# 800U_R3N3_SONSER_V1_0.net
KiCad netlist of a schematic drawn in Altium Designer
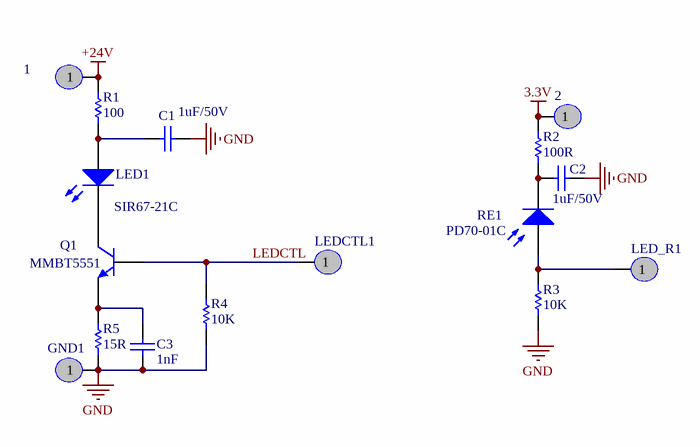
[diagram p0: 800U R3N3_SONSER_V1.0.SchDoc]

(export (version "E")
  (design (tool "Eeschema 10.0.6"))
  (components
    (comp (ref "1") (value "~") (footprint "HOLE_SMD") (libsource (lib "MODBUS_V1.0") (part "焊盘")))
    (comp (ref "2") (value "~") (footprint "HOLE_SMD") (libsource (lib "") (part "焊盘_1")))
    (comp (ref "C1")
      (value "1uF/50V")
      (footprint "C0805")
      (description "贴片电容")
      (fields (field (name "Comment") "105") (field (name "PUBLISHER") "Altium Limited"))
      (libsource (lib "TMJD1.0") (part "Cap"))
    )
    (comp (ref "C2")
      (value "1uF/50V")
      (footprint "C0603")
      (description "贴片电容")
      (fields (field (name "Comment") "105") (field (name "PUBLISHER") "Altium Limited"))
      (libsource (lib "TMJD1.0") (part "Cap"))
    )
    (comp (ref "C3")
      (value "1nF")
      (footprint "C0603")
      (description "贴片电容")
      (fields (field (name "Comment") "102") (field (name "PUBLISHER") "Altium Limited"))
      (libsource (lib "TMJD1.0") (part "Cap"))
    )
    (comp (ref "GND1") (value "~") (footprint "HOLE_SMD") (libsource (lib "MODBUS_V1.0") (part "焊盘")))
    (comp (ref "LED1")
      (value "SIR67-21C")
      (footprint "LED-3.5X2.8")
      (description "贴片红外发射管")
      (fields (field (name "PUBLISHER") "Altium Limited"))
      (libsource (lib "Miscellaneous Devices") (part "LED0"))
    )
    (comp (ref "LEDCTL1") (value "~") (footprint "HOLE_SMD") (libsource (lib "MODBUS_V1.0") (part "焊盘")))
    (comp (ref "LED_R1") (value "~") (footprint "HOLE_SMD") (libsource (lib "") (part "焊盘_1")))
    (comp (ref "Q1")
      (value "MMBT5551")
      (footprint "SOT-23")
      (description "贴片NPN三极管")
      (libsource (lib "Miscellaneous Devices") (part "NPN"))
    )
    (comp (ref "R1")
      (value "100")
      (footprint "R0805")
      (description "贴片电阻")
      (libsource (lib "Miscellaneous Devices") (part "Res Semi"))
    )
    (comp (ref "R2")
      (value "100R")
      (footprint "R0603")
      (description "贴片电阻")
      (fields (field (name "Comment") "100"))
      (libsource (lib "Miscellaneous Devices") (part "Res Semi"))
    )
    (comp (ref "R3")
      (value "10K")
      (footprint "R0603")
      (description "贴片电阻")
      (libsource (lib "Miscellaneous Devices") (part "Res Semi"))
    )
    (comp (ref "R4")
      (value "10K")
      (footprint "R0603")
      (description "贴片电阻")
      (libsource (lib "Miscellaneous Devices") (part "Res Semi"))
    )
    (comp (ref "R5")
      (value "15R")
      (footprint "R0805")
      (description "贴片电阻")
      (fields (field (name "Comment") "15"))
      (libsource (lib "Miscellaneous Devices") (part "Res Semi"))
    )
    (comp (ref "RE1")
      (value "PD70-01C")
      (footprint "LED9*4")
      (description "贴片接收管")
      (fields (field (name "PUBLISHER") "Altium Limited"))
      (libsource (lib "Miscellaneous Devices") (part "Photo Sen"))
    )
  )
  (nets
    (net (code "1") (name "+24V") (class "Default")
      (node (ref "1") (pin "1") (pinfunction "1_1") (pintype "passive"))
      (node (ref "R1") (pin "2") (pinfunction "2_2") (pintype "passive"))
    )
    (net (code "2") (name "/LEDCTL") (class "Default")
      (node (ref "LEDCTL1") (pin "1") (pinfunction "1_1") (pintype "passive"))
      (node (ref "Q1") (pin "1") (pinfunction "B_1") (pintype "passive"))
      (node (ref "R4") (pin "2") (pinfunction "2_2") (pintype "passive"))
    )
    (net (code "3") (name "3.3V") (class "Default")
      (node (ref "2") (pin "1") (pinfunction "1_1") (pintype "passive"))
      (node (ref "R2") (pin "2") (pinfunction "2_2") (pintype "passive"))
    )
    (net (code "4") (name "GND") (class "Default")
      (node (ref "C1") (pin "2") (pinfunction "2_2") (pintype "passive"))
      (node (ref "C2") (pin "2") (pinfunction "2_2") (pintype "passive"))
      (node (ref "C3") (pin "2") (pinfunction "2_2") (pintype "passive"))
      (node (ref "GND1") (pin "1") (pinfunction "1_1") (pintype "passive"))
      (node (ref "R3") (pin "1") (pinfunction "1_1") (pintype "passive"))
      (node (ref "R4") (pin "1") (pinfunction "1_1") (pintype "passive"))
      (node (ref "R5") (pin "1") (pinfunction "1_1") (pintype "passive"))
    )
    (net (code "5") (name "Net-(LED1-A)") (class "Default")
      (node (ref "C1") (pin "1") (pinfunction "1_1") (pintype "passive"))
      (node (ref "LED1") (pin "1") (pinfunction "A_1") (pintype "passive"))
      (node (ref "R1") (pin "1") (pinfunction "1_1") (pintype "passive"))
    )
    (net (code "6") (name "Net-(LED1-K)") (class "Default")
      (node (ref "LED1") (pin "2") (pinfunction "K_2") (pintype "passive"))
      (node (ref "Q1") (pin "3") (pinfunction "C_3") (pintype "passive"))
    )
    (net (code "7") (name "Net-(Q1-E)") (class "Default")
      (node (ref "C3") (pin "1") (pinfunction "1_1") (pintype "passive"))
      (node (ref "Q1") (pin "2") (pinfunction "E_2") (pintype "passive"))
      (node (ref "R5") (pin "2") (pinfunction "2_2") (pintype "passive"))
    )
    (net (code "8") (name "Net-(RE1-A)") (class "Default")
      (node (ref "LED_R1") (pin "1") (pinfunction "1_1") (pintype "passive"))
      (node (ref "R3") (pin "2") (pinfunction "2_2") (pintype "passive"))
      (node (ref "RE1") (pin "1") (pinfunction "A_1") (pintype "passive"))
    )
    (net (code "9") (name "Net-(RE1-K)") (class "Default")
      (node (ref "C2") (pin "1") (pinfunction "1_1") (pintype "passive"))
      (node (ref "R2") (pin "1") (pinfunction "1_1") (pintype "passive"))
      (node (ref "RE1") (pin "2") (pinfunction "K_2") (pintype "passive"))
    )
  )
)
